# HGS_Reflector.net
KiCad netlist of a schematic drawn in EAGLE
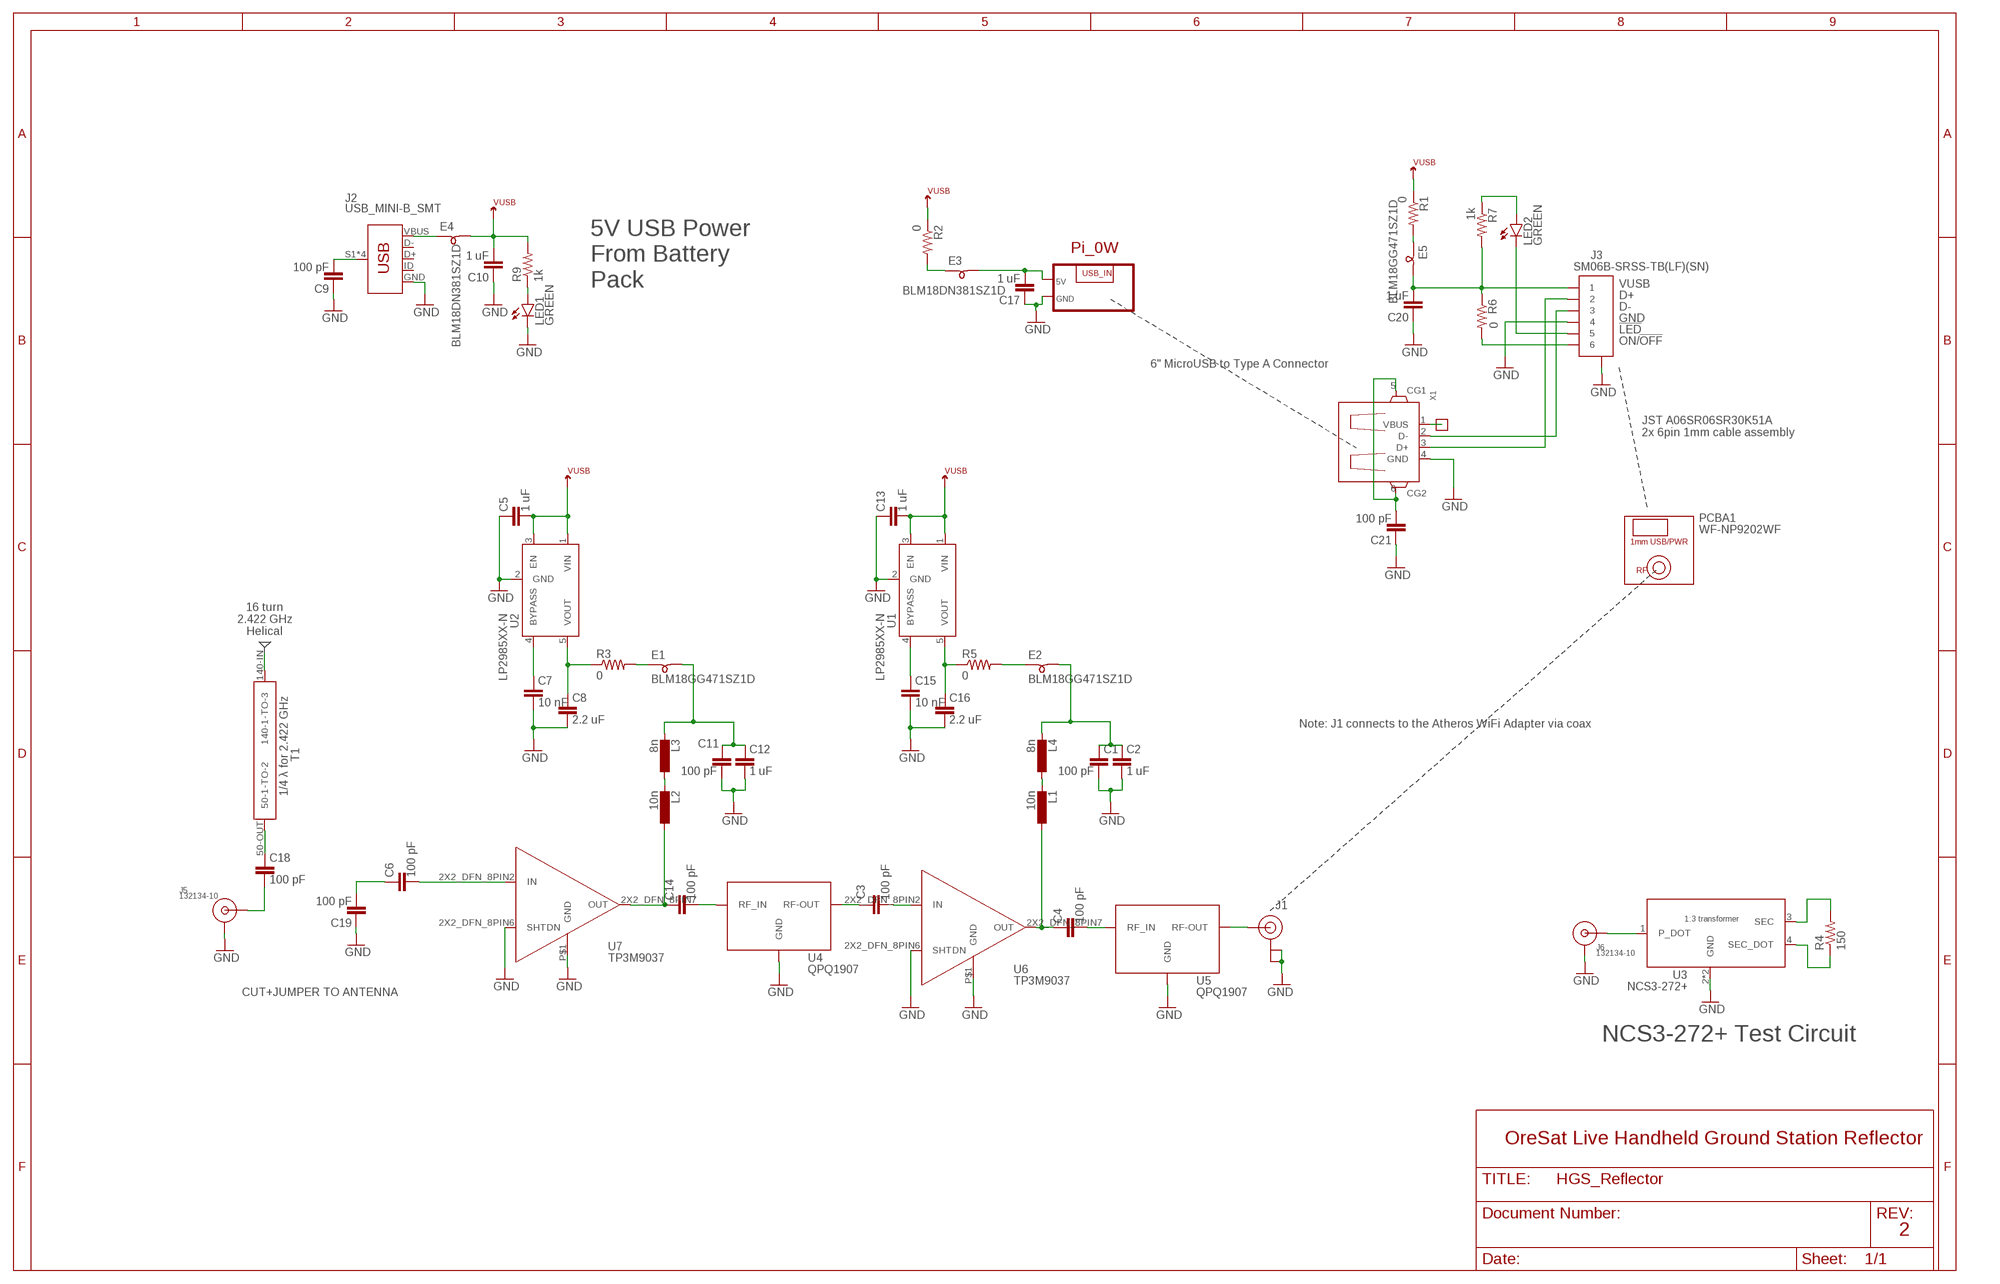
[diagram p0: schematic, sheet 1]

(export (version "E")
  (design (tool "Eeschema 10.0.6"))
  (components
    (comp (ref "C1")
      (value "100 pF")
      (footprint "eagle-import:.0603-B-NOSILK")
      (libsource (lib "eagle-import") (part "C-EU0603-B-NOSILK"))
    )
    (comp (ref "C2")
      (value "1 uF")
      (footprint "eagle-import:.0603-B-NOSILK")
      (libsource (lib "eagle-import") (part "C-EU0603-B-NOSILK"))
    )
    (comp (ref "C3")
      (value "100 pF")
      (footprint "eagle-import:.0402-C-NOSILK")
      (libsource (lib "eagle-import") (part "C-EU0402-C-NOSILK"))
    )
    (comp (ref "C4")
      (value "100 pF")
      (footprint "eagle-import:.0402-C-NOSILK")
      (libsource (lib "eagle-import") (part "C-EU0402-C-NOSILK"))
    )
    (comp (ref "C5")
      (value "1 uF")
      (footprint "eagle-import:.0603-B-NOSILK")
      (libsource (lib "eagle-import") (part "C-EU0603-B-NOSILK"))
    )
    (comp (ref "C6")
      (value "100 pF")
      (footprint "eagle-import:.0402-C-NOSILK")
      (libsource (lib "eagle-import") (part "C-EU0402-C-NOSILK"))
    )
    (comp (ref "C7")
      (value "10 nF")
      (footprint "eagle-import:.0603-B-NOSILK")
      (libsource (lib "eagle-import") (part "C-EU0603-B-NOSILK"))
    )
    (comp (ref "C8")
      (value "2.2 uF")
      (footprint "eagle-import:.0603-B-NOSILK")
      (libsource (lib "eagle-import") (part "C-EU0603-B-NOSILK"))
    )
    (comp (ref "C9")
      (value "100 pF")
      (footprint "eagle-import:.0603-C-NOSILK")
      (libsource (lib "eagle-import") (part "C-EU0603-C-NOSILK"))
    )
    (comp (ref "C10")
      (value "1 uF")
      (footprint "eagle-import:.0603-B-NOSILK")
      (libsource (lib "eagle-import") (part "C-EU0603-B-NOSILK"))
    )
    (comp (ref "C11")
      (value "100 pF")
      (footprint "eagle-import:.0603-B-NOSILK")
      (libsource (lib "eagle-import") (part "C-EU0603-B-NOSILK"))
    )
    (comp (ref "C12")
      (value "1 uF")
      (footprint "eagle-import:.0603-B-NOSILK")
      (libsource (lib "eagle-import") (part "C-EU0603-B-NOSILK"))
    )
    (comp (ref "C13")
      (value "1 uF")
      (footprint "eagle-import:.0603-B-NOSILK")
      (libsource (lib "eagle-import") (part "C-EU0603-B-NOSILK"))
    )
    (comp (ref "C14")
      (value "100 pF")
      (footprint "eagle-import:.0402-C-NOSILK")
      (libsource (lib "eagle-import") (part "C-EU0402-C-NOSILK"))
    )
    (comp (ref "C15")
      (value "10 nF")
      (footprint "eagle-import:.0603-B-NOSILK")
      (libsource (lib "eagle-import") (part "C-EU0603-B-NOSILK"))
    )
    (comp (ref "C16")
      (value "2.2 uF")
      (footprint "eagle-import:.0603-B-NOSILK")
      (libsource (lib "eagle-import") (part "C-EU0603-B-NOSILK"))
    )
    (comp (ref "C17")
      (value "1 uF")
      (footprint "eagle-import:.0603-B-NOSILK")
      (libsource (lib "eagle-import") (part "C-EU0603-B-NOSILK"))
    )
    (comp (ref "C18")
      (value "100 pF")
      (footprint "eagle-import:.0402-C-NOSILK")
      (libsource (lib "eagle-import") (part "C-EU0402-C-NOSILK"))
    )
    (comp (ref "C19")
      (value "100 pF")
      (footprint "eagle-import:.0402-C-NOSILK")
      (libsource (lib "eagle-import") (part "C-EU0402-C-NOSILK"))
    )
    (comp (ref "C20")
      (value "1 uF")
      (footprint "eagle-import:.0603-B-NOSILK")
      (libsource (lib "eagle-import") (part "C-EU0603-B-NOSILK"))
    )
    (comp (ref "C21")
      (value "100 pF")
      (footprint "eagle-import:.0603-C-NOSILK")
      (libsource (lib "eagle-import") (part "C-EU0603-C-NOSILK"))
    )
    (comp (ref "E1")
      (value "BLM18GG471SZ1D")
      (footprint "eagle-import:.0603-B")
      (libsource (lib "eagle-import") (part "L-BEAD-0603-B"))
    )
    (comp (ref "E2")
      (value "BLM18GG471SZ1D")
      (footprint "eagle-import:.0603-B")
      (libsource (lib "eagle-import") (part "L-BEAD-0603-B"))
    )
    (comp (ref "E3")
      (value "BLM18DN381SZ1D")
      (footprint "eagle-import:.0603-B")
      (libsource (lib "eagle-import") (part "L-BEAD-0603-B"))
    )
    (comp (ref "E4")
      (value "BLM18DN381SZ1D")
      (footprint "eagle-import:.0603-B")
      (libsource (lib "eagle-import") (part "L-BEAD-0603-B"))
    )
    (comp (ref "E5")
      (value "BLM18GG471SZ1D")
      (footprint "eagle-import:.0603-B")
      (libsource (lib "eagle-import") (part "L-BEAD-0603-B"))
    )
    (comp (ref "J1")
      (value "U.FL")
      (footprint "eagle-import:U.FL")
      (libsource (lib "eagle-import") (part "U.FL"))
    )
    (comp (ref "J2")
      (value "USB_MINI-B_SMT")
      (footprint "eagle-import:USB-MINIB")
      (libsource (lib "eagle-import") (part "USB_MINI-B_SMT"))
    )
    (comp (ref "J3")
      (value "SM06B-SRSS-TB(LF)(SN)")
      (footprint "eagle-import:CONN_SM06B-SRSS-TB_JST")
      (fields (field (name "COPYRIGHT") "Copyright (C) 2018 Accelerated Designs. All rights reserved"))
      (libsource (lib "eagle-import") (part "SM06B-SRSS-TB(LF)(SN)"))
    )
    (comp (ref "J5")
      (value "132134-10")
      (footprint "eagle-import:132134-10")
      (libsource (lib "eagle-import") (part "132134-10"))
    )
    (comp (ref "J6")
      (value "132134-10")
      (footprint "eagle-import:132134-10")
      (libsource (lib "eagle-import") (part "132134-10"))
    )
    (comp (ref "L1")
      (value "10n")
      (footprint "eagle-import:L3216C")
      (fields (field (name "SPICEPREFIX") "L") (field (name "IMPEDANCE") "10 nH"))
      (libsource (lib "eagle-import") (part "L-EUL3216C"))
    )
    (comp (ref "L2")
      (value "10n")
      (footprint "eagle-import:L3216C")
      (fields (field (name "SPICEPREFIX") "10 nH"))
      (libsource (lib "eagle-import") (part "L-EUL3216C"))
    )
    (comp (ref "L3")
      (value "8n")
      (footprint "eagle-import:L3216C")
      (fields (field (name "SPICEPREFIX") "L") (field (name "IMPEDANCE") "8 nH"))
      (libsource (lib "eagle-import") (part "L-EUL3216C"))
    )
    (comp (ref "L4")
      (value "8n")
      (footprint "eagle-import:L3216C")
      (fields (field (name "SPICEPREFIX") "L") (field (name "IMPEDANCE") "8 nH"))
      (libsource (lib "eagle-import") (part "L-EUL3216C"))
    )
    (comp (ref "LED1")
      (value "GREEN")
      (footprint "eagle-import:LED-0603")
      (libsource (lib "eagle-import") (part "LED-GREEN0603"))
    )
    (comp (ref "LED2")
      (value "GREEN")
      (footprint "eagle-import:LED-0603")
      (libsource (lib "eagle-import") (part "LED-GREEN0603"))
    )
    (comp (ref "PCBA1")
      (value "WF-NP9202WF")
      (footprint "eagle-import:WF-NP9202")
      (libsource (lib "eagle-import") (part "WF-NP9202WF"))
    )
    (comp (ref "R1")
      (value "0")
      (footprint "eagle-import:.0603-B-NOSILK")
      (libsource (lib "eagle-import") (part "R-US_0603-B-NOSILK"))
    )
    (comp (ref "R2")
      (value "0")
      (footprint "eagle-import:.0603-B-NOSILK")
      (libsource (lib "eagle-import") (part "R-US_0603-B-NOSILK"))
    )
    (comp (ref "R3")
      (value "0")
      (footprint "eagle-import:.0603-B-NOSILK")
      (libsource (lib "eagle-import") (part "R-US_0603-B-NOSILK"))
    )
    (comp (ref "R4")
      (value "150")
      (footprint "eagle-import:.0402-C-NOSILK")
      (libsource (lib "eagle-import") (part "R-US_0402-C-NOSILK"))
    )
    (comp (ref "R5")
      (value "0")
      (footprint "eagle-import:.0603-B-NOSILK")
      (libsource (lib "eagle-import") (part "R-US_0603-B-NOSILK"))
    )
    (comp (ref "R6")
      (value "0")
      (footprint "eagle-import:.0603-B-NOSILK")
      (libsource (lib "eagle-import") (part "R-US_0603-B-NOSILK"))
    )
    (comp (ref "R7")
      (value "1k")
      (footprint "eagle-import:.0603-B-NOSILK")
      (libsource (lib "eagle-import") (part "R-US_0603-B-NOSILK"))
    )
    (comp (ref "R9")
      (value "1k")
      (footprint "eagle-import:.0603-B-NOSILK")
      (libsource (lib "eagle-import") (part "R-US_0603-B-NOSILK"))
    )
    (comp (ref "T1")
      (value "QWT2.4222")
      (footprint "eagle-import:QWT_2.422G-V2")
      (libsource (lib "eagle-import") (part "QWT2.4222"))
    )
    (comp (ref "TP2")
      (value "TEST-POINT-LARGE-SQUARE")
      (footprint "eagle-import:1X01")
      (libsource (lib "eagle-import") (part "TEST-POINT-LARGE-SQUARE"))
    )
    (comp (ref "U$5")
      (value "RASP_PI_0WPI_0W")
      (footprint "eagle-import:RASP_PI_0W")
      (libsource (lib "eagle-import") (part "RASP_PI_0WPI_0W"))
    )
    (comp (ref "U1")
      (value "LP2985XX-N")
      (footprint "eagle-import:SOT-23")
      (libsource (lib "eagle-import") (part "LP2985XX-N"))
    )
    (comp (ref "U2")
      (value "LP2985XX-N")
      (footprint "eagle-import:SOT-23")
      (libsource (lib "eagle-import") (part "LP2985XX-N"))
    )
    (comp (ref "U3")
      (value "NCS3-272+")
      (footprint "eagle-import:GE0805C-1")
      (libsource (lib "eagle-import") (part "NCS3-272+"))
    )
    (comp (ref "U4")
      (value "QPQ1907")
      (footprint "eagle-import:QPQ1907")
      (libsource (lib "eagle-import") (part "QPQ1907"))
    )
    (comp (ref "U5")
      (value "QPQ1907")
      (footprint "eagle-import:QPQ1907")
      (libsource (lib "eagle-import") (part "QPQ1907"))
    )
    (comp (ref "U6")
      (value "LNA-TP3M9037")
      (footprint "eagle-import:TP3M9037")
      (libsource (lib "eagle-import") (part "LNA-TP3M9037"))
    )
    (comp (ref "U7")
      (value "LNA-TP3M9037")
      (footprint "eagle-import:TP3M9037")
      (libsource (lib "eagle-import") (part "LNA-TP3M9037"))
    )
    (comp (ref "X1")
      (value "USB_HOST_W/CHASSIS_GND")
      (footprint "eagle-import:GHI2_USB_HOST_HORIZONTAL_W_CHASSIS_GND")
      (libsource (lib "eagle-import") (part "USB_HOST_W/CHASSIS_GND"))
    )
  )
  (nets
    (net (code "1") (name "GND") (class "Default")
      (node (ref "C1") (pin "2") (pinfunction "2_2") (pintype "passive"))
      (node (ref "C10") (pin "1") (pinfunction "1_1") (pintype "passive"))
      (node (ref "C11") (pin "2") (pinfunction "2_2") (pintype "passive"))
      (node (ref "C12") (pin "2") (pinfunction "2_2") (pintype "passive"))
      (node (ref "C13") (pin "1") (pinfunction "1_1") (pintype "passive"))
      (node (ref "C15") (pin "2") (pinfunction "2_2") (pintype "passive"))
      (node (ref "C16") (pin "2") (pinfunction "2_2") (pintype "passive"))
      (node (ref "C17") (pin "1") (pinfunction "1_1") (pintype "passive"))
      (node (ref "C19") (pin "1") (pinfunction "1_1") (pintype "passive"))
      (node (ref "C2") (pin "2") (pinfunction "2_2") (pintype "passive"))
      (node (ref "C20") (pin "1") (pinfunction "1_1") (pintype "passive"))
      (node (ref "C21") (pin "1") (pinfunction "1_1") (pintype "passive"))
      (node (ref "C5") (pin "1") (pinfunction "1_1") (pintype "passive"))
      (node (ref "C7") (pin "2") (pinfunction "2_2") (pintype "passive"))
      (node (ref "C8") (pin "2") (pinfunction "2_2") (pintype "passive"))
      (node (ref "C9") (pin "1") (pinfunction "1_1") (pintype "passive"))
      (node (ref "J1") (pin "1") (pinfunction "GND_1") (pintype "bidirectional"))
      (node (ref "J1") (pin "2") (pinfunction "GND_2") (pintype "bidirectional"))
      (node (ref "J2") (pin "GND") (pinfunction "GND_GND") (pintype "power_in"))
      (node (ref "J3") (pin "4") (pinfunction "4_4") (pintype "passive"))
      (node (ref "J3") (pin "7") (pinfunction "7_7") (pintype "passive"))
      (node (ref "J3") (pin "8") (pinfunction "7_8") (pintype "passive"))
      (node (ref "J5") (pin "SHIELD") (pinfunction "GND_SHIELD") (pintype "passive"))
      (node (ref "J6") (pin "SHIELD") (pinfunction "GND_SHIELD") (pintype "passive"))
      (node (ref "LED1") (pin "C") (pinfunction "C_C") (pintype "passive"))
      (node (ref "U$5") (pin "GND") (pinfunction "GND_GND") (pintype "bidirectional"))
      (node (ref "U1") (pin "2") (pinfunction "GND_2") (pintype "power_in"))
      (node (ref "U2") (pin "2") (pinfunction "GND_2") (pintype "power_in"))
      (node (ref "U3") (pin "2") (pinfunction "GND_2") (pintype "power_in"))
      (node (ref "U3") (pin "5") (pinfunction "GND_5") (pintype "power_in"))
      (node (ref "U4") (pin "GND") (pinfunction "GND_GND") (pintype "power_in"))
      (node (ref "U4") (pin "GND2") (pinfunction "GND_GND2") (pintype "power_in"))
      (node (ref "U4") (pin "GND3") (pinfunction "GND_GND3") (pintype "power_in"))
      (node (ref "U5") (pin "GND") (pinfunction "GND_GND") (pintype "power_in"))
      (node (ref "U5") (pin "GND2") (pinfunction "GND_GND2") (pintype "power_in"))
      (node (ref "U5") (pin "GND3") (pinfunction "GND_GND3") (pintype "power_in"))
      (node (ref "U6") (pin "2X2_DFN_8PIN6") (pinfunction "SHTDN_2X2_DFN_8PIN6") (pintype "power_in"))
      (node (ref "U6") (pin "P$1") (pinfunction "GND_P$1") (pintype "power_in"))
      (node (ref "U7") (pin "2X2_DFN_8PIN6") (pinfunction "SHTDN_2X2_DFN_8PIN6") (pintype "power_in"))
      (node (ref "U7") (pin "P$1") (pinfunction "GND_P$1") (pintype "power_in"))
      (node (ref "X1") (pin "4") (pinfunction "GND_4") (pintype "bidirectional"))
    )
    (net (code "2") (name "Net-(C1-Pad1)") (class "Default")
      (node (ref "C1") (pin "1") (pinfunction "1_1") (pintype "passive"))
      (node (ref "C2") (pin "1") (pinfunction "1_1") (pintype "passive"))
      (node (ref "E2") (pin "2") (pinfunction "2_2") (pintype "passive"))
      (node (ref "L4") (pin "2") (pinfunction "2_2") (pintype "passive"))
    )
    (net (code "3") (name "Net-(C9-Pad2)") (class "Default")
      (node (ref "C9") (pin "2") (pinfunction "2_2") (pintype "passive"))
      (node (ref "J2") (pin "S1") (pinfunction "SHIELD_S1") (pintype "bidirectional"))
      (node (ref "J2") (pin "S2") (pinfunction "SHIELD_S2") (pintype "bidirectional"))
      (node (ref "J2") (pin "S3") (pinfunction "SHIELD_S3") (pintype "bidirectional"))
      (node (ref "J2") (pin "S4") (pinfunction "SHIELD_S4") (pintype "bidirectional"))
    )
    (net (code "4") (name "Net-(C11-Pad1)") (class "Default")
      (node (ref "C11") (pin "1") (pinfunction "1_1") (pintype "passive"))
      (node (ref "C12") (pin "1") (pinfunction "1_1") (pintype "passive"))
      (node (ref "E1") (pin "2") (pinfunction "2_2") (pintype "passive"))
      (node (ref "L3") (pin "2") (pinfunction "2_2") (pintype "passive"))
    )
    (net (code "5") (name "Net-(C17-Pad2)") (class "Default")
      (node (ref "C17") (pin "2") (pinfunction "2_2") (pintype "passive"))
      (node (ref "E3") (pin "2") (pinfunction "2_2") (pintype "passive"))
      (node (ref "U$5") (pin "5V") (pinfunction "5V_5V") (pintype "bidirectional"))
    )
    (net (code "6") (name "Net-(C19-Pad2)") (class "Default")
      (node (ref "C19") (pin "2") (pinfunction "2_2") (pintype "passive"))
      (node (ref "C6") (pin "1") (pinfunction "1_1") (pintype "passive"))
    )
    (net (code "7") (name "Net-(C20-Pad2)") (class "Default")
      (node (ref "C20") (pin "2") (pinfunction "2_2") (pintype "passive"))
      (node (ref "E5") (pin "2") (pinfunction "2_2") (pintype "passive"))
      (node (ref "J3") (pin "1") (pinfunction "1_1") (pintype "passive"))
      (node (ref "R6") (pin "1") (pinfunction "1_1") (pintype "passive"))
      (node (ref "R7") (pin "2") (pinfunction "2_2") (pintype "passive"))
    )
    (net (code "8") (name "Net-(E1-Pad1)") (class "Default")
      (node (ref "E1") (pin "1") (pinfunction "1_1") (pintype "passive"))
      (node (ref "R3") (pin "2") (pinfunction "2_2") (pintype "passive"))
    )
    (net (code "9") (name "Net-(E2-Pad1)") (class "Default")
      (node (ref "E2") (pin "1") (pinfunction "1_1") (pintype "passive"))
      (node (ref "R5") (pin "2") (pinfunction "2_2") (pintype "passive"))
    )
    (net (code "10") (name "Net-(E3-Pad1)") (class "Default")
      (node (ref "E3") (pin "1") (pinfunction "1_1") (pintype "passive"))
      (node (ref "R2") (pin "2") (pinfunction "2_2") (pintype "passive"))
    )
    (net (code "11") (name "Net-(E4-Pad1)") (class "Default")
      (node (ref "E4") (pin "1") (pinfunction "1_1") (pintype "passive"))
      (node (ref "J2") (pin "VBUS") (pinfunction "VBUS_VBUS") (pintype "power_in"))
    )
    (net (code "12") (name "Net-(E5-Pad1)") (class "Default")
      (node (ref "E5") (pin "1") (pinfunction "1_1") (pintype "passive"))
      (node (ref "R1") (pin "2") (pinfunction "2_2") (pintype "passive"))
    )
    (net (code "13") (name "Net-(J1-SIGNAL)") (class "Default")
      (node (ref "J1") (pin "FEED") (pinfunction "SIGNAL_FEED") (pintype "bidirectional"))
      (node (ref "U5") (pin "OUTPUT") (pinfunction "RF-OUT_OUTPUT") (pintype "passive"))
    )
    (net (code "14") (name "Net-(J3-Pad5)") (class "Default")
      (node (ref "J3") (pin "5") (pinfunction "5_5") (pintype "passive"))
      (node (ref "LED2") (pin "C") (pinfunction "C_C") (pintype "passive"))
    )
    (net (code "15") (name "Net-(J3-Pad6)") (class "Default")
      (node (ref "J3") (pin "6") (pinfunction "6_6") (pintype "passive"))
      (node (ref "R6") (pin "2") (pinfunction "2_2") (pintype "passive"))
    )
    (net (code "16") (name "Net-(J5-SIG)") (class "Default")
      (node (ref "C18") (pin "2") (pinfunction "2_2") (pintype "passive"))
      (node (ref "J5") (pin "CENTER") (pinfunction "SIG_CENTER") (pintype "passive"))
    )
    (net (code "17") (name "Net-(J6-SIG)") (class "Default")
      (node (ref "J6") (pin "CENTER") (pinfunction "SIG_CENTER") (pintype "passive"))
      (node (ref "U3") (pin "1") (pinfunction "P_DOT_1") (pintype "passive"))
    )
    (net (code "18") (name "Net-(L1-Pad2)") (class "Default")
      (node (ref "L1") (pin "2") (pinfunction "2_2") (pintype "passive"))
      (node (ref "L4") (pin "1") (pinfunction "1_1") (pintype "passive"))
    )
    (net (code "19") (name "Net-(L2-Pad2)") (class "Default")
      (node (ref "L2") (pin "2") (pinfunction "2_2") (pintype "passive"))
      (node (ref "L3") (pin "1") (pinfunction "1_1") (pintype "passive"))
    )
    (net (code "20") (name "Net-(LED1-PadA)") (class "Default")
      (node (ref "LED1") (pin "A") (pinfunction "A_A") (pintype "passive"))
      (node (ref "R9") (pin "1") (pinfunction "1_1") (pintype "passive"))
    )
    (net (code "21") (name "Net-(LED2-PadA)") (class "Default")
      (node (ref "LED2") (pin "A") (pinfunction "A_A") (pintype "passive"))
      (node (ref "R7") (pin "1") (pinfunction "1_1") (pintype "passive"))
    )
    (net (code "22") (name "Net-(T1-50-1-TO-2)") (class "Default")
      (node (ref "C18") (pin "1") (pinfunction "1_1") (pintype "passive"))
      (node (ref "T1") (pin "50-OUT") (pinfunction "50-1-TO-2_50-OUT") (pintype "passive"))
    )
    (net (code "23") (name "Net-(U1-BYPASS)") (class "Default")
      (node (ref "C15") (pin "1") (pinfunction "1_1") (pintype "passive"))
      (node (ref "U1") (pin "4") (pinfunction "BYPASS_4") (pintype "power_in"))
    )
    (net (code "24") (name "Net-(U1-VOUT)") (class "Default")
      (node (ref "C16") (pin "1") (pinfunction "1_1") (pintype "passive"))
      (node (ref "R5") (pin "1") (pinfunction "1_1") (pintype "passive"))
      (node (ref "U1") (pin "5") (pinfunction "VOUT_5") (pintype "power_in"))
    )
    (net (code "25") (name "Net-(U2-BYPASS)") (class "Default")
      (node (ref "C7") (pin "1") (pinfunction "1_1") (pintype "passive"))
      (node (ref "U2") (pin "4") (pinfunction "BYPASS_4") (pintype "power_in"))
    )
    (net (code "26") (name "Net-(U2-VOUT)") (class "Default")
      (node (ref "C8") (pin "1") (pinfunction "1_1") (pintype "passive"))
      (node (ref "R3") (pin "1") (pinfunction "1_1") (pintype "passive"))
      (node (ref "U2") (pin "5") (pinfunction "VOUT_5") (pintype "power_in"))
    )
    (net (code "27") (name "Net-(U3-SEC)") (class "Default")
      (node (ref "R4") (pin "2") (pinfunction "2_2") (pintype "passive"))
      (node (ref "U3") (pin "3") (pinfunction "SEC_3") (pintype "passive"))
    )
    (net (code "28") (name "Net-(U3-SEC_DOT)") (class "Default")
      (node (ref "R4") (pin "1") (pinfunction "1_1") (pintype "passive"))
      (node (ref "U3") (pin "4") (pinfunction "SEC_DOT_4") (pintype "passive"))
    )
    (net (code "29") (name "Net-(U4-RF-OUT)") (class "Default")
      (node (ref "C3") (pin "1") (pinfunction "1_1") (pintype "passive"))
      (node (ref "U4") (pin "OUTPUT") (pinfunction "RF-OUT_OUTPUT") (pintype "passive"))
    )
    (net (code "30") (name "Net-(U4-RF_IN)") (class "Default")
      (node (ref "C14") (pin "2") (pinfunction "2_2") (pintype "passive"))
      (node (ref "U4") (pin "INPUT") (pinfunction "RF_IN_INPUT") (pintype "passive"))
    )
    (net (code "31") (name "Net-(U5-RF_IN)") (class "Default")
      (node (ref "C4") (pin "2") (pinfunction "2_2") (pintype "passive"))
      (node (ref "U5") (pin "INPUT") (pinfunction "RF_IN_INPUT") (pintype "passive"))
    )
    (net (code "32") (name "Net-(U6-IN)") (class "Default")
      (node (ref "C3") (pin "2") (pinfunction "2_2") (pintype "passive"))
      (node (ref "U6") (pin "2X2_DFN_8PIN2") (pinfunction "IN_2X2_DFN_8PIN2") (pintype "bidirectional"))
    )
    (net (code "33") (name "Net-(U6-OUT)") (class "Default")
      (node (ref "C4") (pin "1") (pinfunction "1_1") (pintype "passive"))
      (node (ref "L1") (pin "1") (pinfunction "1_1") (pintype "passive"))
      (node (ref "U6") (pin "2X2_DFN_8PIN7") (pinfunction "OUT_2X2_DFN_8PIN7") (pintype "bidirectional"))
    )
    (net (code "34") (name "Net-(U7-IN)") (class "Default")
      (node (ref "C6") (pin "2") (pinfunction "2_2") (pintype "passive"))
      (node (ref "U7") (pin "2X2_DFN_8PIN2") (pinfunction "IN_2X2_DFN_8PIN2") (pintype "bidirectional"))
    )
    (net (code "35") (name "Net-(U7-OUT)") (class "Default")
      (node (ref "C14") (pin "1") (pinfunction "1_1") (pintype "passive"))
      (node (ref "L2") (pin "1") (pinfunction "1_1") (pintype "passive"))
      (node (ref "U7") (pin "2X2_DFN_8PIN7") (pinfunction "OUT_2X2_DFN_8PIN7") (pintype "bidirectional"))
    )
    (net (code "36") (name "Net-(X1-CG1)") (class "Default")
      (node (ref "C21") (pin "2") (pinfunction "2_2") (pintype "passive"))
      (node (ref "X1") (pin "5") (pinfunction "CG1_5") (pintype "bidirectional"))
      (node (ref "X1") (pin "6") (pinfunction "CG2_6") (pintype "bidirectional"))
    )
    (net (code "37") (name "Net-(X1-D+)") (class "Default")
      (node (ref "J3") (pin "2") (pinfunction "2_2") (pintype "passive"))
      (node (ref "X1") (pin "3") (pinfunction "D+_3") (pintype "bidirectional"))
    )
    (net (code "38") (name "Net-(X1-D-)") (class "Default")
      (node (ref "J3") (pin "3") (pinfunction "3_3") (pintype "passive"))
      (node (ref "X1") (pin "2") (pinfunction "D-_2") (pintype "bidirectional"))
    )
    (net (code "39") (name "Net-(X1-VBUS)") (class "Default")
      (node (ref "TP2") (pin "1") (pinfunction "1_1") (pintype "passive"))
      (node (ref "X1") (pin "1") (pinfunction "VBUS_1") (pintype "bidirectional"))
    )
    (net (code "40") (name "VUSB") (class "Default")
      (node (ref "C10") (pin "2") (pinfunction "2_2") (pintype "passive"))
      (node (ref "C13") (pin "2") (pinfunction "2_2") (pintype "passive"))
      (node (ref "C5") (pin "2") (pinfunction "2_2") (pintype "passive"))
      (node (ref "E4") (pin "2") (pinfunction "2_2") (pintype "passive"))
      (node (ref "R1") (pin "1") (pinfunction "1_1") (pintype "passive"))
      (node (ref "R2") (pin "1") (pinfunction "1_1") (pintype "passive"))
      (node (ref "R9") (pin "2") (pinfunction "2_2") (pintype "passive"))
      (node (ref "U1") (pin "1") (pinfunction "VIN_1") (pintype "power_in"))
      (node (ref "U1") (pin "3") (pinfunction "EN_3") (pintype "input"))
      (node (ref "U2") (pin "1") (pinfunction "VIN_1") (pintype "power_in"))
      (node (ref "U2") (pin "3") (pinfunction "EN_3") (pintype "input"))
    )
    (net (code "41") (name "unconnected-(J2-PadD+)") (class "Default")
      (node (ref "J2") (pin "D+") (pinfunction "D+_D+") (pintype "bidirectional"))
    )
    (net (code "42") (name "unconnected-(J2-PadD-)") (class "Default")
      (node (ref "J2") (pin "D-") (pinfunction "D-_D-") (pintype "bidirectional"))
    )
    (net (code "43") (name "unconnected-(J2-PadID)") (class "Default")
      (node (ref "J2") (pin "ID") (pinfunction "ID_ID") (pintype "bidirectional"))
    )
    (net (code "44") (name "unconnected-(T1-140-1-TO-3-Pad140-IN)") (class "Default")
      (node (ref "T1") (pin "140-IN") (pinfunction "140-1-TO-3_140-IN") (pintype "passive"))
    )
  )
)
